# Hammerhead_-_MAX11300_Breakout_Connector.net
KiCad netlist of a schematic drawn in Altium Designer
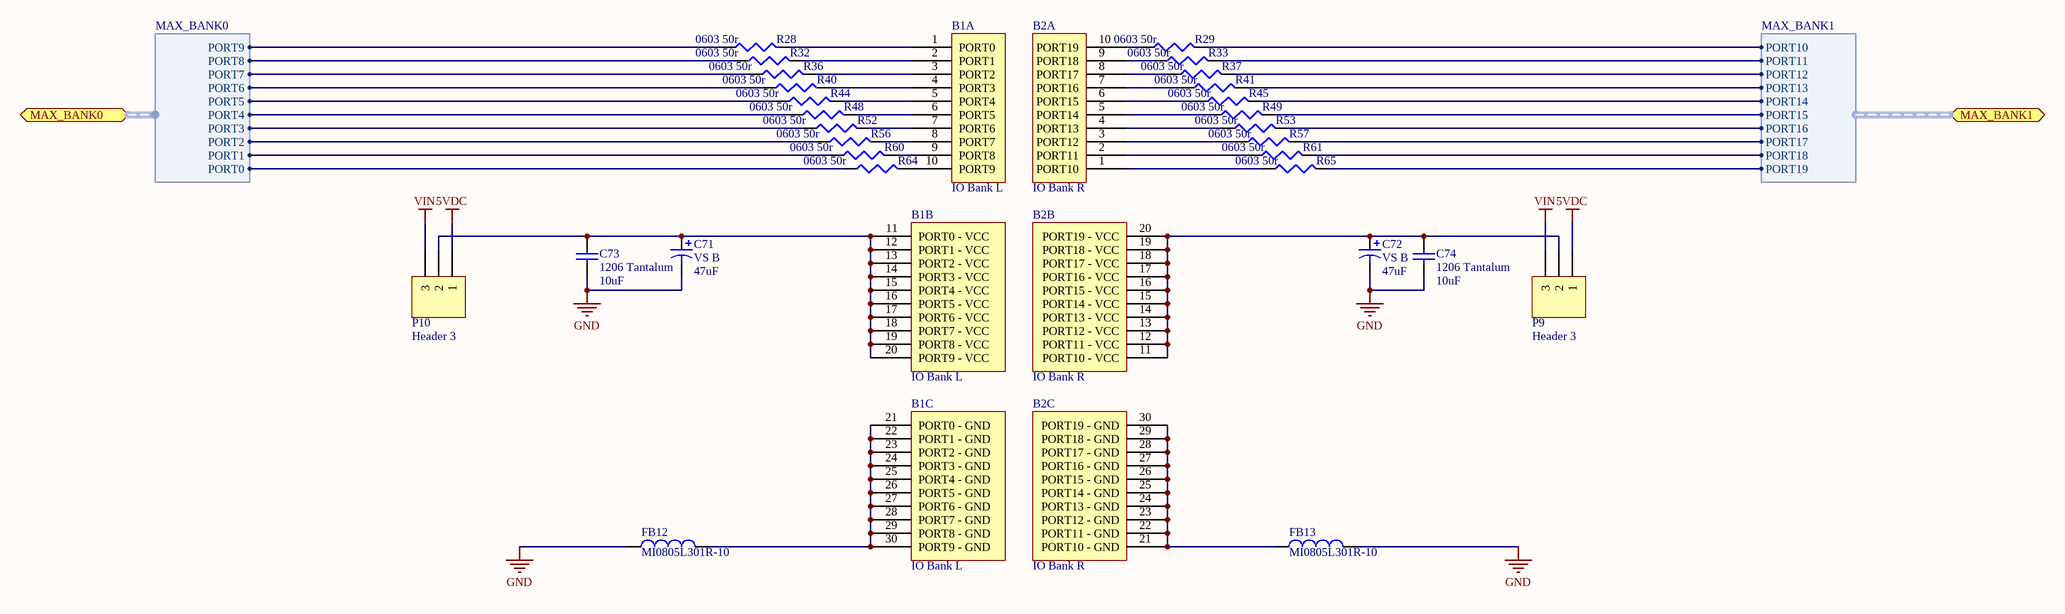
[diagram p0: Hammerhead - MAX11300 Breakout Connectors R1.1.SchDoc]

(export (version "E")
  (design (tool "Eeschema 10.0.6"))
  (components
    (comp (ref "B1")
      (value "IO Bank L")
      (footprint "2.54mm 10X3 Header")
      (libsource (lib "SunIO Schematic Symbol Lib") (part "IO Bank L"))
    )
    (comp (ref "B2")
      (value "IO Bank R")
      (footprint "2.54mm 10X3 Header")
      (libsource (lib "SunIO Schematic Symbol Lib") (part "IO Bank R"))
    )
    (comp (ref "C71")
      (value "VS B")
      (footprint "Panasonic VS B")
      (description "Polarized Capacitor (Radial)")
      (fields (field (name "ALTIUM_VALUE") "47uF") (field (name "PUBLISHER") "Altium Limited"))
      (libsource (lib "Miscellaneous Devices") (part "Cap Pol1"))
    )
    (comp (ref "C72")
      (value "VS B")
      (footprint "Panasonic VS B")
      (description "Polarized Capacitor (Radial)")
      (fields (field (name "ALTIUM_VALUE") "47uF") (field (name "PUBLISHER") "Altium Limited"))
      (libsource (lib "Miscellaneous Devices") (part "Cap Pol1"))
    )
    (comp (ref "C73")
      (value "1206 Tantalum")
      (footprint "C1206")
      (description "Capacitor (Semiconductor SIM Model)")
      (fields (field (name "ALTIUM_VALUE") "10uF") (field (name "PUBLISHER") "Altium Limited"))
      (libsource (lib "Miscellaneous Devices") (part "Cap Semi"))
    )
    (comp (ref "C74")
      (value "1206 Tantalum")
      (footprint "C1206")
      (description "Capacitor (Semiconductor SIM Model)")
      (fields (field (name "ALTIUM_VALUE") "10uF") (field (name "PUBLISHER") "Altium Limited"))
      (libsource (lib "Miscellaneous Devices") (part "Cap Semi"))
    )
    (comp (ref "FB12")
      (value "MI0805L301R-10")
      (footprint "SM 0805 - gap trimmed")
      (description "Inductor")
      (fields (field (name "PUBLISHER") "Altium Limited"))
      (libsource (lib "Miscellaneous Devices") (part "Inductor"))
    )
    (comp (ref "FB13")
      (value "MI0805L301R-10")
      (footprint "SM 0805 - gap trimmed")
      (description "Inductor")
      (fields (field (name "PUBLISHER") "Altium Limited"))
      (libsource (lib "Miscellaneous Devices") (part "Inductor"))
    )
    (comp (ref "P9")
      (value "Header 3")
      (footprint "HDR1X3")
      (description "Header, 3-Pin")
      (fields (field (name "PUBLISHER") "Altium Limited"))
      (libsource (lib "Miscellaneous Connectors") (part "Header 3"))
    )
    (comp (ref "P10")
      (value "Header 3")
      (footprint "HDR1X3")
      (description "Header, 3-Pin")
      (fields (field (name "PUBLISHER") "Altium Limited"))
      (libsource (lib "Miscellaneous Connectors") (part "Header 3"))
    )
    (comp (ref "R28")
      (value "0603")
      (footprint "J1-0603")
      (description "Resistor")
      (fields (field (name "ALTIUM_VALUE") "50r") (field (name "PUBLISHER") "Altium Limited"))
      (libsource (lib "Miscellaneous Devices") (part "Res3"))
    )
    (comp (ref "R29")
      (value "0603")
      (footprint "J1-0603")
      (description "Resistor")
      (fields (field (name "ALTIUM_VALUE") "50r") (field (name "PUBLISHER") "Altium Limited"))
      (libsource (lib "Miscellaneous Devices") (part "Res3"))
    )
    (comp (ref "R32")
      (value "0603")
      (footprint "J1-0603")
      (description "Resistor")
      (fields (field (name "ALTIUM_VALUE") "50r") (field (name "PUBLISHER") "Altium Limited"))
      (libsource (lib "Miscellaneous Devices") (part "Res3"))
    )
    (comp (ref "R33")
      (value "0603")
      (footprint "J1-0603")
      (description "Resistor")
      (fields (field (name "ALTIUM_VALUE") "50r") (field (name "PUBLISHER") "Altium Limited"))
      (libsource (lib "Miscellaneous Devices") (part "Res3"))
    )
    (comp (ref "R36")
      (value "0603")
      (footprint "J1-0603")
      (description "Resistor")
      (fields (field (name "ALTIUM_VALUE") "50r") (field (name "PUBLISHER") "Altium Limited"))
      (libsource (lib "Miscellaneous Devices") (part "Res3"))
    )
    (comp (ref "R37")
      (value "0603")
      (footprint "J1-0603")
      (description "Resistor")
      (fields (field (name "ALTIUM_VALUE") "50r") (field (name "PUBLISHER") "Altium Limited"))
      (libsource (lib "Miscellaneous Devices") (part "Res3"))
    )
    (comp (ref "R40")
      (value "0603")
      (footprint "J1-0603")
      (description "Resistor")
      (fields (field (name "ALTIUM_VALUE") "50r") (field (name "PUBLISHER") "Altium Limited"))
      (libsource (lib "Miscellaneous Devices") (part "Res3"))
    )
    (comp (ref "R41")
      (value "0603")
      (footprint "J1-0603")
      (description "Resistor")
      (fields (field (name "ALTIUM_VALUE") "50r") (field (name "PUBLISHER") "Altium Limited"))
      (libsource (lib "Miscellaneous Devices") (part "Res3"))
    )
    (comp (ref "R44")
      (value "0603")
      (footprint "J1-0603")
      (description "Resistor")
      (fields (field (name "ALTIUM_VALUE") "50r") (field (name "PUBLISHER") "Altium Limited"))
      (libsource (lib "Miscellaneous Devices") (part "Res3"))
    )
    (comp (ref "R45")
      (value "0603")
      (footprint "J1-0603")
      (description "Resistor")
      (fields (field (name "ALTIUM_VALUE") "50r") (field (name "PUBLISHER") "Altium Limited"))
      (libsource (lib "Miscellaneous Devices") (part "Res3"))
    )
    (comp (ref "R48")
      (value "0603")
      (footprint "J1-0603")
      (description "Resistor")
      (fields (field (name "ALTIUM_VALUE") "50r") (field (name "PUBLISHER") "Altium Limited"))
      (libsource (lib "Miscellaneous Devices") (part "Res3"))
    )
    (comp (ref "R49")
      (value "0603")
      (footprint "J1-0603")
      (description "Resistor")
      (fields (field (name "ALTIUM_VALUE") "50r") (field (name "PUBLISHER") "Altium Limited"))
      (libsource (lib "Miscellaneous Devices") (part "Res3"))
    )
    (comp (ref "R52")
      (value "0603")
      (footprint "J1-0603")
      (description "Resistor")
      (fields (field (name "ALTIUM_VALUE") "50r") (field (name "PUBLISHER") "Altium Limited"))
      (libsource (lib "Miscellaneous Devices") (part "Res3"))
    )
    (comp (ref "R53")
      (value "0603")
      (footprint "J1-0603")
      (description "Resistor")
      (fields (field (name "ALTIUM_VALUE") "50r") (field (name "PUBLISHER") "Altium Limited"))
      (libsource (lib "Miscellaneous Devices") (part "Res3"))
    )
    (comp (ref "R56")
      (value "0603")
      (footprint "J1-0603")
      (description "Resistor")
      (fields (field (name "ALTIUM_VALUE") "50r") (field (name "PUBLISHER") "Altium Limited"))
      (libsource (lib "Miscellaneous Devices") (part "Res3"))
    )
    (comp (ref "R57")
      (value "0603")
      (footprint "J1-0603")
      (description "Resistor")
      (fields (field (name "ALTIUM_VALUE") "50r") (field (name "PUBLISHER") "Altium Limited"))
      (libsource (lib "Miscellaneous Devices") (part "Res3"))
    )
    (comp (ref "R60")
      (value "0603")
      (footprint "J1-0603")
      (description "Resistor")
      (fields (field (name "ALTIUM_VALUE") "50r") (field (name "PUBLISHER") "Altium Limited"))
      (libsource (lib "Miscellaneous Devices") (part "Res3"))
    )
    (comp (ref "R61")
      (value "0603")
      (footprint "J1-0603")
      (description "Resistor")
      (fields (field (name "ALTIUM_VALUE") "50r") (field (name "PUBLISHER") "Altium Limited"))
      (libsource (lib "Miscellaneous Devices") (part "Res3"))
    )
    (comp (ref "R64")
      (value "0603")
      (footprint "J1-0603")
      (description "Resistor")
      (fields (field (name "ALTIUM_VALUE") "50r") (field (name "PUBLISHER") "Altium Limited"))
      (libsource (lib "Miscellaneous Devices") (part "Res3"))
    )
    (comp (ref "R65")
      (value "0603")
      (footprint "J1-0603")
      (description "Resistor")
      (fields (field (name "ALTIUM_VALUE") "50r") (field (name "PUBLISHER") "Altium Limited"))
      (libsource (lib "Miscellaneous Devices") (part "Res3"))
    )
  )
  (nets
    (net (code "3") (name "/PORT0") (class "Default")
      (node (ref "R64") (pin "1") (pinfunction "1_1") (pintype "passive"))
    )
    (net (code "4") (name "/PORT1") (class "Default")
      (node (ref "R60") (pin "1") (pinfunction "1_1") (pintype "passive"))
    )
    (net (code "5") (name "/PORT2") (class "Default")
      (node (ref "R56") (pin "1") (pinfunction "1_1") (pintype "passive"))
    )
    (net (code "6") (name "/PORT3") (class "Default")
      (node (ref "R52") (pin "1") (pinfunction "1_1") (pintype "passive"))
    )
    (net (code "7") (name "/PORT4") (class "Default")
      (node (ref "R48") (pin "1") (pinfunction "1_1") (pintype "passive"))
    )
    (net (code "8") (name "/PORT5") (class "Default")
      (node (ref "R44") (pin "1") (pinfunction "1_1") (pintype "passive"))
    )
    (net (code "9") (name "/PORT6") (class "Default")
      (node (ref "R40") (pin "1") (pinfunction "1_1") (pintype "passive"))
    )
    (net (code "10") (name "/PORT7") (class "Default")
      (node (ref "R36") (pin "1") (pinfunction "1_1") (pintype "passive"))
    )
    (net (code "11") (name "/PORT8") (class "Default")
      (node (ref "R32") (pin "1") (pinfunction "1_1") (pintype "passive"))
    )
    (net (code "12") (name "/PORT9") (class "Default")
      (node (ref "R28") (pin "1") (pinfunction "1_1") (pintype "passive"))
    )
    (net (code "13") (name "/PORT10") (class "Default")
      (node (ref "R29") (pin "2") (pinfunction "2_2") (pintype "passive"))
    )
    (net (code "14") (name "/PORT11") (class "Default")
      (node (ref "R33") (pin "2") (pinfunction "2_2") (pintype "passive"))
    )
    (net (code "15") (name "/PORT12") (class "Default")
      (node (ref "R37") (pin "2") (pinfunction "2_2") (pintype "passive"))
    )
    (net (code "16") (name "/PORT13") (class "Default")
      (node (ref "R41") (pin "2") (pinfunction "2_2") (pintype "passive"))
    )
    (net (code "17") (name "/PORT14") (class "Default")
      (node (ref "R45") (pin "2") (pinfunction "2_2") (pintype "passive"))
    )
    (net (code "18") (name "/PORT15") (class "Default")
      (node (ref "R49") (pin "2") (pinfunction "2_2") (pintype "passive"))
    )
    (net (code "19") (name "/PORT16") (class "Default")
      (node (ref "R53") (pin "2") (pinfunction "2_2") (pintype "passive"))
    )
    (net (code "20") (name "/PORT17") (class "Default")
      (node (ref "R57") (pin "2") (pinfunction "2_2") (pintype "passive"))
    )
    (net (code "21") (name "/PORT18") (class "Default")
      (node (ref "R61") (pin "2") (pinfunction "2_2") (pintype "passive"))
    )
    (net (code "22") (name "/PORT19") (class "Default")
      (node (ref "R65") (pin "2") (pinfunction "2_2") (pintype "passive"))
    )
    (net (code "25") (name "5VDC") (class "Default")
      (node (ref "P10") (pin "1") (pinfunction "1_1") (pintype "passive"))
      (node (ref "P9") (pin "1") (pinfunction "1_1") (pintype "passive"))
    )
    (net (code "26") (name "GND") (class "Default")
      (node (ref "C71") (pin "2") (pinfunction "2_2") (pintype "passive"))
      (node (ref "C72") (pin "2") (pinfunction "2_2") (pintype "passive"))
      (node (ref "C73") (pin "1") (pinfunction "1_1") (pintype "passive"))
      (node (ref "C74") (pin "1") (pinfunction "1_1") (pintype "passive"))
      (node (ref "FB12") (pin "1") (pinfunction "1_1") (pintype "passive"))
      (node (ref "FB13") (pin "2") (pinfunction "2_2") (pintype "passive"))
    )
    (net (code "27") (name "Net-(B1A-PORT0)") (class "Default")
      (node (ref "B1") (pin "1") (pinfunction "PORT0_1") (pintype "passive"))
      (node (ref "R28") (pin "2") (pinfunction "2_2") (pintype "passive"))
    )
    (net (code "28") (name "Net-(B1A-PORT1)") (class "Default")
      (node (ref "B1") (pin "2") (pinfunction "PORT1_2") (pintype "passive"))
      (node (ref "R32") (pin "2") (pinfunction "2_2") (pintype "passive"))
    )
    (net (code "29") (name "Net-(B1A-PORT2)") (class "Default")
      (node (ref "B1") (pin "3") (pinfunction "PORT2_3") (pintype "passive"))
      (node (ref "R36") (pin "2") (pinfunction "2_2") (pintype "passive"))
    )
    (net (code "30") (name "Net-(B1A-PORT3)") (class "Default")
      (node (ref "B1") (pin "4") (pinfunction "PORT3_4") (pintype "passive"))
      (node (ref "R40") (pin "2") (pinfunction "2_2") (pintype "passive"))
    )
    (net (code "31") (name "Net-(B1A-PORT4)") (class "Default")
      (node (ref "B1") (pin "5") (pinfunction "PORT4_5") (pintype "passive"))
      (node (ref "R44") (pin "2") (pinfunction "2_2") (pintype "passive"))
    )
    (net (code "32") (name "Net-(B1A-PORT5)") (class "Default")
      (node (ref "B1") (pin "6") (pinfunction "PORT5_6") (pintype "passive"))
      (node (ref "R48") (pin "2") (pinfunction "2_2") (pintype "passive"))
    )
    (net (code "33") (name "Net-(B1A-PORT6)") (class "Default")
      (node (ref "B1") (pin "7") (pinfunction "PORT6_7") (pintype "passive"))
      (node (ref "R52") (pin "2") (pinfunction "2_2") (pintype "passive"))
    )
    (net (code "34") (name "Net-(B1A-PORT7)") (class "Default")
      (node (ref "B1") (pin "8") (pinfunction "PORT7_8") (pintype "passive"))
      (node (ref "R56") (pin "2") (pinfunction "2_2") (pintype "passive"))
    )
    (net (code "35") (name "Net-(B1A-PORT8)") (class "Default")
      (node (ref "B1") (pin "9") (pinfunction "PORT8_9") (pintype "passive"))
      (node (ref "R60") (pin "2") (pinfunction "2_2") (pintype "passive"))
    )
    (net (code "36") (name "Net-(B1A-PORT9)") (class "Default")
      (node (ref "B1") (pin "10") (pinfunction "PORT9_10") (pintype "passive"))
      (node (ref "R64") (pin "2") (pinfunction "2_2") (pintype "passive"))
    )
    (net (code "37") (name "Net-(B1B-PORT0_-_VCC)") (class "Default")
      (node (ref "B1") (pin "11") (pinfunction "PORT0_-_VCC_11") (pintype "passive"))
      (node (ref "B1") (pin "12") (pinfunction "PORT1_-_VCC_12") (pintype "passive"))
      (node (ref "B1") (pin "13") (pinfunction "PORT2_-_VCC_13") (pintype "passive"))
      (node (ref "B1") (pin "14") (pinfunction "PORT3_-_VCC_14") (pintype "passive"))
      (node (ref "B1") (pin "15") (pinfunction "PORT4_-_VCC_15") (pintype "passive"))
      (node (ref "B1") (pin "16") (pinfunction "PORT5_-_VCC_16") (pintype "passive"))
      (node (ref "B1") (pin "17") (pinfunction "PORT6_-_VCC_17") (pintype "passive"))
      (node (ref "B1") (pin "18") (pinfunction "PORT7_-_VCC_18") (pintype "passive"))
      (node (ref "B1") (pin "19") (pinfunction "PORT8_-_VCC_19") (pintype "passive"))
      (node (ref "B1") (pin "20") (pinfunction "PORT9_-_VCC_20") (pintype "passive"))
      (node (ref "C71") (pin "1") (pinfunction "1_1") (pintype "passive"))
      (node (ref "C73") (pin "2") (pinfunction "2_2") (pintype "passive"))
      (node (ref "P10") (pin "2") (pinfunction "2_2") (pintype "passive"))
    )
    (net (code "38") (name "Net-(B1C-PORT0_-_GND)") (class "Default")
      (node (ref "B1") (pin "21") (pinfunction "PORT0_-_GND_21") (pintype "passive"))
      (node (ref "B1") (pin "22") (pinfunction "PORT1_-_GND_22") (pintype "passive"))
      (node (ref "B1") (pin "23") (pinfunction "PORT2_-_GND_23") (pintype "passive"))
      (node (ref "B1") (pin "24") (pinfunction "PORT3_-_GND_24") (pintype "passive"))
      (node (ref "B1") (pin "25") (pinfunction "PORT4_-_GND_25") (pintype "passive"))
      (node (ref "B1") (pin "26") (pinfunction "PORT5_-_GND_26") (pintype "passive"))
      (node (ref "B1") (pin "27") (pinfunction "PORT6_-_GND_27") (pintype "passive"))
      (node (ref "B1") (pin "28") (pinfunction "PORT7_-_GND_28") (pintype "passive"))
      (node (ref "B1") (pin "29") (pinfunction "PORT8_-_GND_29") (pintype "passive"))
      (node (ref "B1") (pin "30") (pinfunction "PORT9_-_GND_30") (pintype "passive"))
      (node (ref "FB12") (pin "2") (pinfunction "2_2") (pintype "passive"))
    )
    (net (code "39") (name "Net-(B2A-PORT10)") (class "Default")
      (node (ref "B2") (pin "1") (pinfunction "PORT10_1") (pintype "passive"))
      (node (ref "R65") (pin "1") (pinfunction "1_1") (pintype "passive"))
    )
    (net (code "40") (name "Net-(B2A-PORT11)") (class "Default")
      (node (ref "B2") (pin "2") (pinfunction "PORT11_2") (pintype "passive"))
      (node (ref "R61") (pin "1") (pinfunction "1_1") (pintype "passive"))
    )
    (net (code "41") (name "Net-(B2A-PORT12)") (class "Default")
      (node (ref "B2") (pin "3") (pinfunction "PORT12_3") (pintype "passive"))
      (node (ref "R57") (pin "1") (pinfunction "1_1") (pintype "passive"))
    )
    (net (code "42") (name "Net-(B2A-PORT13)") (class "Default")
      (node (ref "B2") (pin "4") (pinfunction "PORT13_4") (pintype "passive"))
      (node (ref "R53") (pin "1") (pinfunction "1_1") (pintype "passive"))
    )
    (net (code "43") (name "Net-(B2A-PORT14)") (class "Default")
      (node (ref "B2") (pin "5") (pinfunction "PORT14_5") (pintype "passive"))
      (node (ref "R49") (pin "1") (pinfunction "1_1") (pintype "passive"))
    )
    (net (code "44") (name "Net-(B2A-PORT15)") (class "Default")
      (node (ref "B2") (pin "6") (pinfunction "PORT15_6") (pintype "passive"))
      (node (ref "R45") (pin "1") (pinfunction "1_1") (pintype "passive"))
    )
    (net (code "45") (name "Net-(B2A-PORT16)") (class "Default")
      (node (ref "B2") (pin "7") (pinfunction "PORT16_7") (pintype "passive"))
      (node (ref "R41") (pin "1") (pinfunction "1_1") (pintype "passive"))
    )
    (net (code "46") (name "Net-(B2A-PORT17)") (class "Default")
      (node (ref "B2") (pin "8") (pinfunction "PORT17_8") (pintype "passive"))
      (node (ref "R37") (pin "1") (pinfunction "1_1") (pintype "passive"))
    )
    (net (code "47") (name "Net-(B2A-PORT18)") (class "Default")
      (node (ref "B2") (pin "9") (pinfunction "PORT18_9") (pintype "passive"))
      (node (ref "R33") (pin "1") (pinfunction "1_1") (pintype "passive"))
    )
    (net (code "48") (name "Net-(B2A-PORT19)") (class "Default")
      (node (ref "B2") (pin "10") (pinfunction "PORT19_10") (pintype "passive"))
      (node (ref "R29") (pin "1") (pinfunction "1_1") (pintype "passive"))
    )
    (net (code "49") (name "Net-(B2B-PORT10_-_VCC)") (class "Default")
      (node (ref "B2") (pin "11") (pinfunction "PORT10_-_VCC_11") (pintype "passive"))
      (node (ref "B2") (pin "12") (pinfunction "PORT11_-_VCC_12") (pintype "passive"))
      (node (ref "B2") (pin "13") (pinfunction "PORT12_-_VCC_13") (pintype "passive"))
      (node (ref "B2") (pin "14") (pinfunction "PORT13_-_VCC_14") (pintype "passive"))
      (node (ref "B2") (pin "15") (pinfunction "PORT14_-_VCC_15") (pintype "passive"))
      (node (ref "B2") (pin "16") (pinfunction "PORT15_-_VCC_16") (pintype "passive"))
      (node (ref "B2") (pin "17") (pinfunction "PORT16_-_VCC_17") (pintype "passive"))
      (node (ref "B2") (pin "18") (pinfunction "PORT17_-_VCC_18") (pintype "passive"))
      (node (ref "B2") (pin "19") (pinfunction "PORT18_-_VCC_19") (pintype "passive"))
      (node (ref "B2") (pin "20") (pinfunction "PORT19_-_VCC_20") (pintype "passive"))
      (node (ref "C72") (pin "1") (pinfunction "1_1") (pintype "passive"))
      (node (ref "C74") (pin "2") (pinfunction "2_2") (pintype "passive"))
      (node (ref "P9") (pin "2") (pinfunction "2_2") (pintype "passive"))
    )
    (net (code "50") (name "Net-(B2C-PORT10_-_GND)") (class "Default")
      (node (ref "B2") (pin "21") (pinfunction "PORT10_-_GND_21") (pintype "passive"))
      (node (ref "B2") (pin "22") (pinfunction "PORT11_-_GND_22") (pintype "passive"))
      (node (ref "B2") (pin "23") (pinfunction "PORT12_-_GND_23") (pintype "passive"))
      (node (ref "B2") (pin "24") (pinfunction "PORT13_-_GND_24") (pintype "passive"))
      (node (ref "B2") (pin "25") (pinfunction "PORT14_-_GND_25") (pintype "passive"))
      (node (ref "B2") (pin "26") (pinfunction "PORT15_-_GND_26") (pintype "passive"))
      (node (ref "B2") (pin "27") (pinfunction "PORT16_-_GND_27") (pintype "passive"))
      (node (ref "B2") (pin "28") (pinfunction "PORT17_-_GND_28") (pintype "passive"))
      (node (ref "B2") (pin "29") (pinfunction "PORT18_-_GND_29") (pintype "passive"))
      (node (ref "B2") (pin "30") (pinfunction "PORT19_-_GND_30") (pintype "passive"))
      (node (ref "FB13") (pin "1") (pinfunction "1_1") (pintype "passive"))
    )
    (net (code "51") (name "VIN") (class "Default")
      (node (ref "P10") (pin "3") (pinfunction "3_3") (pintype "passive"))
      (node (ref "P9") (pin "3") (pinfunction "3_3") (pintype "passive"))
    )
  )
)
